# BBB_Cape_template.net
KiCad netlist of a schematic drawn in Altium Designer
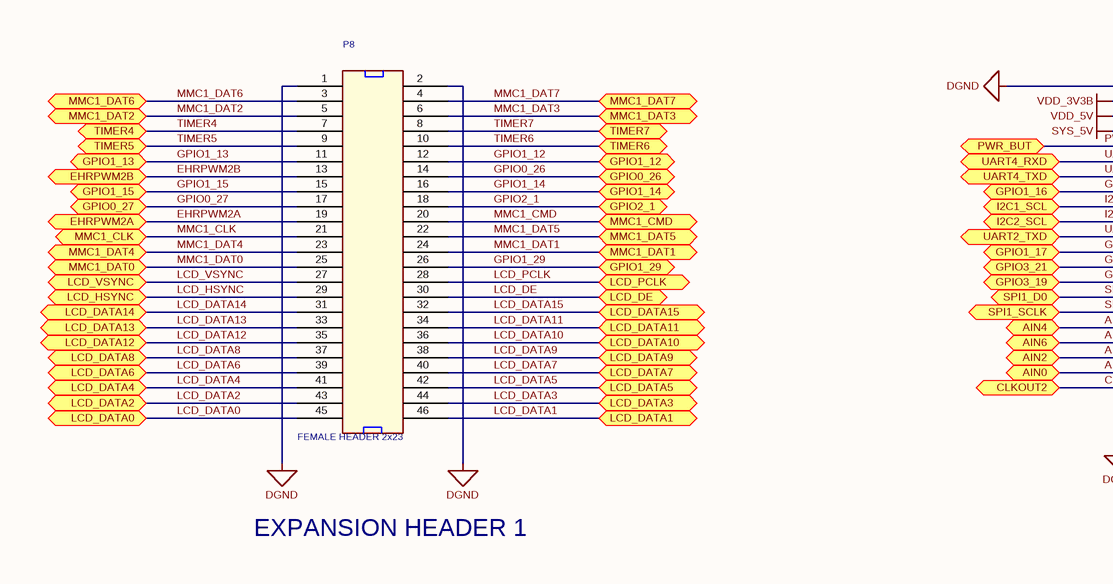
[diagram p0: BBB_Cape_template.SchDoc, left]
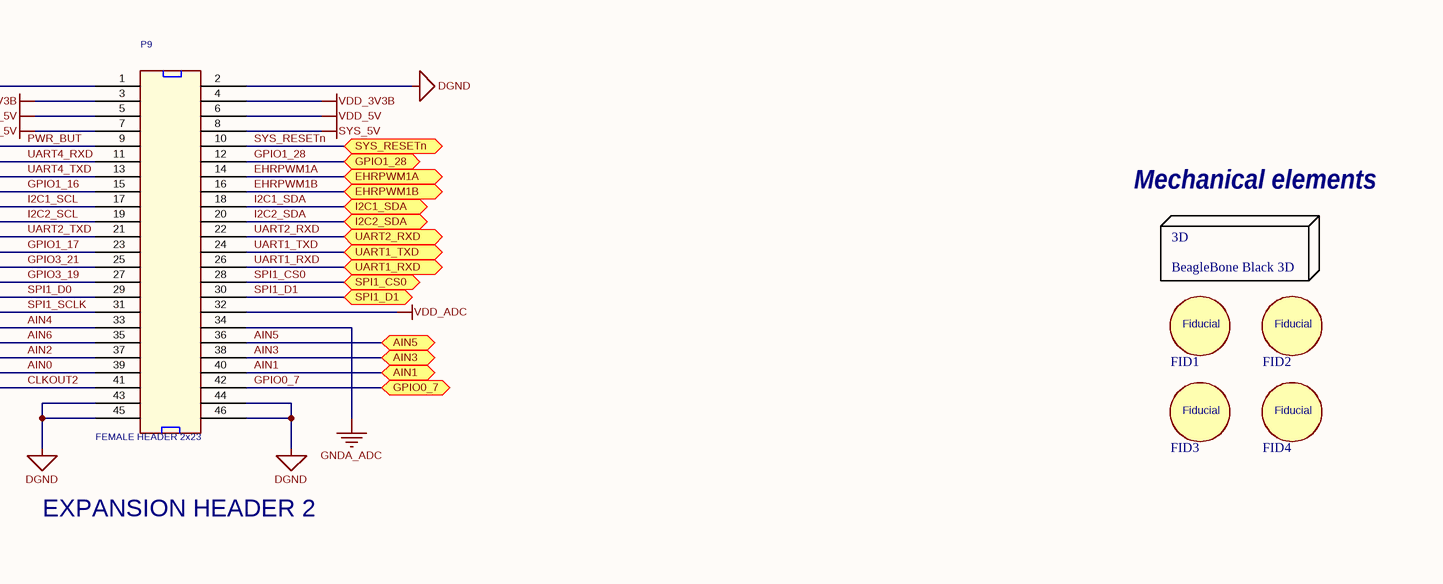
[diagram p1: BBB_Cape_template.SchDoc, right]

(export (version "E")
  (design (tool "Eeschema 10.0.6"))
  (components
    (comp (ref "3D") (value "BeagleBone Black 3D") (libsource (lib "Stamp") (part "BeagleBone Black 3D")))
    (comp (ref "FID1")
      (value "MECH-Fiducial")
      (footprint "S_Fiducial")
      (description "Fiducial")
      (libsource (lib "Stamp") (part "MECH-Fiducial"))
    )
    (comp (ref "FID2")
      (value "MECH-Fiducial")
      (footprint "S_Fiducial")
      (description "Fiducial")
      (libsource (lib "Stamp") (part "MECH-Fiducial"))
    )
    (comp (ref "FID3")
      (value "MECH-Fiducial")
      (footprint "S_Fiducial")
      (description "Fiducial")
      (libsource (lib "Stamp") (part "MECH-Fiducial"))
    )
    (comp (ref "FID4")
      (value "MECH-Fiducial")
      (footprint "S_Fiducial")
      (description "Fiducial")
      (libsource (lib "Stamp") (part "MECH-Fiducial"))
    )
    (comp (ref "P8")
      (value "FEMALE HEADER 2x23")
      (description "CONN HEADER FMAL 46PS.1\" DL GOLD")
      (fields
        (field (name "MANUFACTURER") "Sullins Connector Solutions")
        (field (name "MANUFACTURER PART NUMBER") "PPPC232LFBN-RC")
      )
      (libsource (lib "BEAGLEBONEBLACK_REV A5B") (part "HDR_46_F_2_0.1_0.1"))
    )
    (comp (ref "P9")
      (value "FEMALE HEADER 2x23")
      (description "CONN HEADER FMAL 46PS.1\" DL GOLD")
      (fields
        (field (name "MANUFACTURER") "Sullins Connector Solutions")
        (field (name "MANUFACTURER PART NUMBER") "PPPC232LFBN-RC")
      )
      (libsource (lib "BEAGLEBONEBLACK_REV A5B") (part "HDR_46_F_2_0.1_0.1"))
    )
  )
  (nets
    (net (code "1") (name "/AIN0") (class "Default")
      (node (ref "P9") (pin "39") (pinfunction "20_39") (pintype "passive"))
    )
    (net (code "2") (name "/AIN1") (class "Default")
      (node (ref "P9") (pin "40") (pinfunction "45_40") (pintype "passive"))
    )
    (net (code "3") (name "/AIN2") (class "Default")
      (node (ref "P9") (pin "37") (pinfunction "19_37") (pintype "passive"))
    )
    (net (code "4") (name "/AIN3") (class "Default")
      (node (ref "P9") (pin "38") (pinfunction "44_38") (pintype "passive"))
    )
    (net (code "5") (name "/AIN4") (class "Default")
      (node (ref "P9") (pin "33") (pinfunction "17_33") (pintype "passive"))
    )
    (net (code "6") (name "/AIN5") (class "Default")
      (node (ref "P9") (pin "36") (pinfunction "43_36") (pintype "passive"))
    )
    (net (code "7") (name "/AIN6") (class "Default")
      (node (ref "P9") (pin "35") (pinfunction "18_35") (pintype "passive"))
    )
    (net (code "8") (name "/CLKOUT2") (class "Default")
      (node (ref "P9") (pin "41") (pinfunction "21_41") (pintype "passive"))
    )
    (net (code "9") (name "/EHRPWM1A") (class "Default")
      (node (ref "P9") (pin "14") (pinfunction "32_14") (pintype "passive"))
    )
    (net (code "10") (name "/EHRPWM1B") (class "Default")
      (node (ref "P9") (pin "16") (pinfunction "33_16") (pintype "passive"))
    )
    (net (code "11") (name "/EHRPWM2A") (class "Default")
      (node (ref "P8") (pin "19") (pinfunction "10_19") (pintype "passive"))
    )
    (net (code "12") (name "/EHRPWM2B") (class "Default")
      (node (ref "P8") (pin "13") (pinfunction "7_13") (pintype "passive"))
    )
    (net (code "13") (name "/GPIO0_7") (class "Default")
      (node (ref "P9") (pin "42") (pinfunction "46_42") (pintype "passive"))
    )
    (net (code "14") (name "/GPIO0_26") (class "Default")
      (node (ref "P8") (pin "14") (pinfunction "32_14") (pintype "passive"))
    )
    (net (code "15") (name "/GPIO0_27") (class "Default")
      (node (ref "P8") (pin "17") (pinfunction "9_17") (pintype "passive"))
    )
    (net (code "16") (name "/GPIO1_12") (class "Default")
      (node (ref "P8") (pin "12") (pinfunction "31_12") (pintype "passive"))
    )
    (net (code "17") (name "/GPIO1_13") (class "Default")
      (node (ref "P8") (pin "11") (pinfunction "6_11") (pintype "passive"))
    )
    (net (code "18") (name "/GPIO1_14") (class "Default")
      (node (ref "P8") (pin "16") (pinfunction "33_16") (pintype "passive"))
    )
    (net (code "19") (name "/GPIO1_15") (class "Default")
      (node (ref "P8") (pin "15") (pinfunction "8_15") (pintype "passive"))
    )
    (net (code "20") (name "/GPIO1_16") (class "Default")
      (node (ref "P9") (pin "15") (pinfunction "8_15") (pintype "passive"))
    )
    (net (code "21") (name "/GPIO1_17") (class "Default")
      (node (ref "P9") (pin "23") (pinfunction "12_23") (pintype "passive"))
    )
    (net (code "22") (name "/GPIO1_28") (class "Default")
      (node (ref "P9") (pin "12") (pinfunction "31_12") (pintype "passive"))
    )
    (net (code "23") (name "/GPIO1_29") (class "Default")
      (node (ref "P8") (pin "26") (pinfunction "38_26") (pintype "passive"))
    )
    (net (code "24") (name "/GPIO2_1") (class "Default")
      (node (ref "P8") (pin "18") (pinfunction "34_18") (pintype "passive"))
    )
    (net (code "25") (name "/GPIO3_19") (class "Default")
      (node (ref "P9") (pin "27") (pinfunction "14_27") (pintype "passive"))
    )
    (net (code "26") (name "/GPIO3_21") (class "Default")
      (node (ref "P9") (pin "25") (pinfunction "13_25") (pintype "passive"))
    )
    (net (code "27") (name "/I2C1_SCL") (class "Default")
      (node (ref "P9") (pin "17") (pinfunction "9_17") (pintype "passive"))
    )
    (net (code "28") (name "/I2C1_SDA") (class "Default")
      (node (ref "P9") (pin "18") (pinfunction "34_18") (pintype "passive"))
    )
    (net (code "29") (name "/I2C2_SCL") (class "Default")
      (node (ref "P9") (pin "19") (pinfunction "10_19") (pintype "passive"))
    )
    (net (code "30") (name "/I2C2_SDA") (class "Default")
      (node (ref "P9") (pin "20") (pinfunction "35_20") (pintype "passive"))
    )
    (net (code "31") (name "/LCD_DATA0") (class "Default")
      (node (ref "P8") (pin "45") (pinfunction "23_45") (pintype "passive"))
    )
    (net (code "32") (name "/LCD_DATA1") (class "Default")
      (node (ref "P8") (pin "46") (pinfunction "48_46") (pintype "passive"))
    )
    (net (code "33") (name "/LCD_DATA2") (class "Default")
      (node (ref "P8") (pin "43") (pinfunction "22_43") (pintype "passive"))
    )
    (net (code "34") (name "/LCD_DATA3") (class "Default")
      (node (ref "P8") (pin "44") (pinfunction "47_44") (pintype "passive"))
    )
    (net (code "35") (name "/LCD_DATA4") (class "Default")
      (node (ref "P8") (pin "41") (pinfunction "21_41") (pintype "passive"))
    )
    (net (code "36") (name "/LCD_DATA5") (class "Default")
      (node (ref "P8") (pin "42") (pinfunction "46_42") (pintype "passive"))
    )
    (net (code "37") (name "/LCD_DATA6") (class "Default")
      (node (ref "P8") (pin "39") (pinfunction "20_39") (pintype "passive"))
    )
    (net (code "38") (name "/LCD_DATA7") (class "Default")
      (node (ref "P8") (pin "40") (pinfunction "45_40") (pintype "passive"))
    )
    (net (code "39") (name "/LCD_DATA8") (class "Default")
      (node (ref "P8") (pin "37") (pinfunction "19_37") (pintype "passive"))
    )
    (net (code "40") (name "/LCD_DATA9") (class "Default")
      (node (ref "P8") (pin "38") (pinfunction "44_38") (pintype "passive"))
    )
    (net (code "41") (name "/LCD_DATA10") (class "Default")
      (node (ref "P8") (pin "36") (pinfunction "43_36") (pintype "passive"))
    )
    (net (code "42") (name "/LCD_DATA11") (class "Default")
      (node (ref "P8") (pin "34") (pinfunction "42_34") (pintype "passive"))
    )
    (net (code "43") (name "/LCD_DATA12") (class "Default")
      (node (ref "P8") (pin "35") (pinfunction "18_35") (pintype "passive"))
    )
    (net (code "44") (name "/LCD_DATA13") (class "Default")
      (node (ref "P8") (pin "33") (pinfunction "17_33") (pintype "passive"))
    )
    (net (code "45") (name "/LCD_DATA14") (class "Default")
      (node (ref "P8") (pin "31") (pinfunction "16_31") (pintype "passive"))
    )
    (net (code "46") (name "/LCD_DATA15") (class "Default")
      (node (ref "P8") (pin "32") (pinfunction "41_32") (pintype "passive"))
    )
    (net (code "47") (name "/LCD_DE") (class "Default")
      (node (ref "P8") (pin "30") (pinfunction "40_30") (pintype "passive"))
    )
    (net (code "48") (name "/LCD_HSYNC") (class "Default")
      (node (ref "P8") (pin "29") (pinfunction "15_29") (pintype "passive"))
    )
    (net (code "49") (name "/LCD_PCLK") (class "Default")
      (node (ref "P8") (pin "28") (pinfunction "39_28") (pintype "passive"))
    )
    (net (code "50") (name "/LCD_VSYNC") (class "Default")
      (node (ref "P8") (pin "27") (pinfunction "14_27") (pintype "passive"))
    )
    (net (code "51") (name "/MMC1_CLK") (class "Default")
      (node (ref "P8") (pin "21") (pinfunction "11_21") (pintype "passive"))
    )
    (net (code "52") (name "/MMC1_CMD") (class "Default")
      (node (ref "P8") (pin "20") (pinfunction "35_20") (pintype "passive"))
    )
    (net (code "53") (name "/MMC1_DAT0") (class "Default")
      (node (ref "P8") (pin "25") (pinfunction "13_25") (pintype "passive"))
    )
    (net (code "54") (name "/MMC1_DAT1") (class "Default")
      (node (ref "P8") (pin "24") (pinfunction "37_24") (pintype "passive"))
    )
    (net (code "55") (name "/MMC1_DAT2") (class "Default")
      (node (ref "P8") (pin "5") (pinfunction "3_5") (pintype "passive"))
    )
    (net (code "56") (name "/MMC1_DAT3") (class "Default")
      (node (ref "P8") (pin "6") (pinfunction "28_6") (pintype "passive"))
    )
    (net (code "57") (name "/MMC1_DAT4") (class "Default")
      (node (ref "P8") (pin "23") (pinfunction "12_23") (pintype "passive"))
    )
    (net (code "58") (name "/MMC1_DAT5") (class "Default")
      (node (ref "P8") (pin "22") (pinfunction "36_22") (pintype "passive"))
    )
    (net (code "59") (name "/MMC1_DAT6") (class "Default")
      (node (ref "P8") (pin "3") (pinfunction "2_3") (pintype "passive"))
    )
    (net (code "60") (name "/MMC1_DAT7") (class "Default")
      (node (ref "P8") (pin "4") (pinfunction "27_4") (pintype "passive"))
    )
    (net (code "61") (name "/PWR_BUT") (class "Default")
      (node (ref "P9") (pin "9") (pinfunction "5_9") (pintype "passive"))
    )
    (net (code "62") (name "/SPI1_CS0") (class "Default")
      (node (ref "P9") (pin "28") (pinfunction "39_28") (pintype "passive"))
    )
    (net (code "63") (name "/SPI1_D0") (class "Default")
      (node (ref "P9") (pin "29") (pinfunction "15_29") (pintype "passive"))
    )
    (net (code "64") (name "/SPI1_D1") (class "Default")
      (node (ref "P9") (pin "30") (pinfunction "40_30") (pintype "passive"))
    )
    (net (code "65") (name "/SPI1_SCLK") (class "Default")
      (node (ref "P9") (pin "31") (pinfunction "16_31") (pintype "passive"))
    )
    (net (code "66") (name "/SYS_RESETn") (class "Default")
      (node (ref "P9") (pin "10") (pinfunction "30_10") (pintype "passive"))
    )
    (net (code "67") (name "/TIMER4") (class "Default")
      (node (ref "P8") (pin "7") (pinfunction "4_7") (pintype "passive"))
    )
    (net (code "68") (name "/TIMER5") (class "Default")
      (node (ref "P8") (pin "9") (pinfunction "5_9") (pintype "passive"))
    )
    (net (code "69") (name "/TIMER6") (class "Default")
      (node (ref "P8") (pin "10") (pinfunction "30_10") (pintype "passive"))
    )
    (net (code "70") (name "/TIMER7") (class "Default")
      (node (ref "P8") (pin "8") (pinfunction "29_8") (pintype "passive"))
    )
    (net (code "71") (name "/UART1_RXD") (class "Default")
      (node (ref "P9") (pin "26") (pinfunction "38_26") (pintype "passive"))
    )
    (net (code "72") (name "/UART1_TXD") (class "Default")
      (node (ref "P9") (pin "24") (pinfunction "37_24") (pintype "passive"))
    )
    (net (code "73") (name "/UART2_RXD") (class "Default")
      (node (ref "P9") (pin "22") (pinfunction "36_22") (pintype "passive"))
    )
    (net (code "74") (name "/UART2_TXD") (class "Default")
      (node (ref "P9") (pin "21") (pinfunction "11_21") (pintype "passive"))
    )
    (net (code "75") (name "/UART4_RXD") (class "Default")
      (node (ref "P9") (pin "11") (pinfunction "6_11") (pintype "passive"))
    )
    (net (code "76") (name "/UART4_TXD") (class "Default")
      (node (ref "P9") (pin "13") (pinfunction "7_13") (pintype "passive"))
    )
    (net (code "77") (name "DGND") (class "Default")
      (node (ref "P8") (pin "1") (pinfunction "1_1") (pintype "passive"))
      (node (ref "P8") (pin "2") (pinfunction "26_2") (pintype "passive"))
      (node (ref "P9") (pin "1") (pinfunction "1_1") (pintype "passive"))
      (node (ref "P9") (pin "2") (pinfunction "26_2") (pintype "passive"))
      (node (ref "P9") (pin "43") (pinfunction "22_43") (pintype "passive"))
      (node (ref "P9") (pin "44") (pinfunction "47_44") (pintype "passive"))
      (node (ref "P9") (pin "45") (pinfunction "23_45") (pintype "passive"))
      (node (ref "P9") (pin "46") (pinfunction "48_46") (pintype "passive"))
    )
    (net (code "78") (name "GNDA_ADC") (class "Default")
      (node (ref "P9") (pin "34") (pinfunction "42_34") (pintype "passive"))
    )
    (net (code "79") (name "SYS_5V") (class "Default")
      (node (ref "P9") (pin "7") (pinfunction "4_7") (pintype "passive"))
      (node (ref "P9") (pin "8") (pinfunction "29_8") (pintype "passive"))
    )
    (net (code "80") (name "VDD_3V3B") (class "Default")
      (node (ref "P9") (pin "3") (pinfunction "2_3") (pintype "passive"))
      (node (ref "P9") (pin "4") (pinfunction "27_4") (pintype "passive"))
    )
    (net (code "81") (name "VDD_5V") (class "Default")
      (node (ref "P9") (pin "5") (pinfunction "3_5") (pintype "passive"))
      (node (ref "P9") (pin "6") (pinfunction "28_6") (pintype "passive"))
    )
    (net (code "82") (name "VDD_ADC") (class "Default")
      (node (ref "P9") (pin "32") (pinfunction "41_32") (pintype "passive"))
    )
  )
)
